# esquematico2.net
KiCad netlist of a schematic drawn in EAGLE
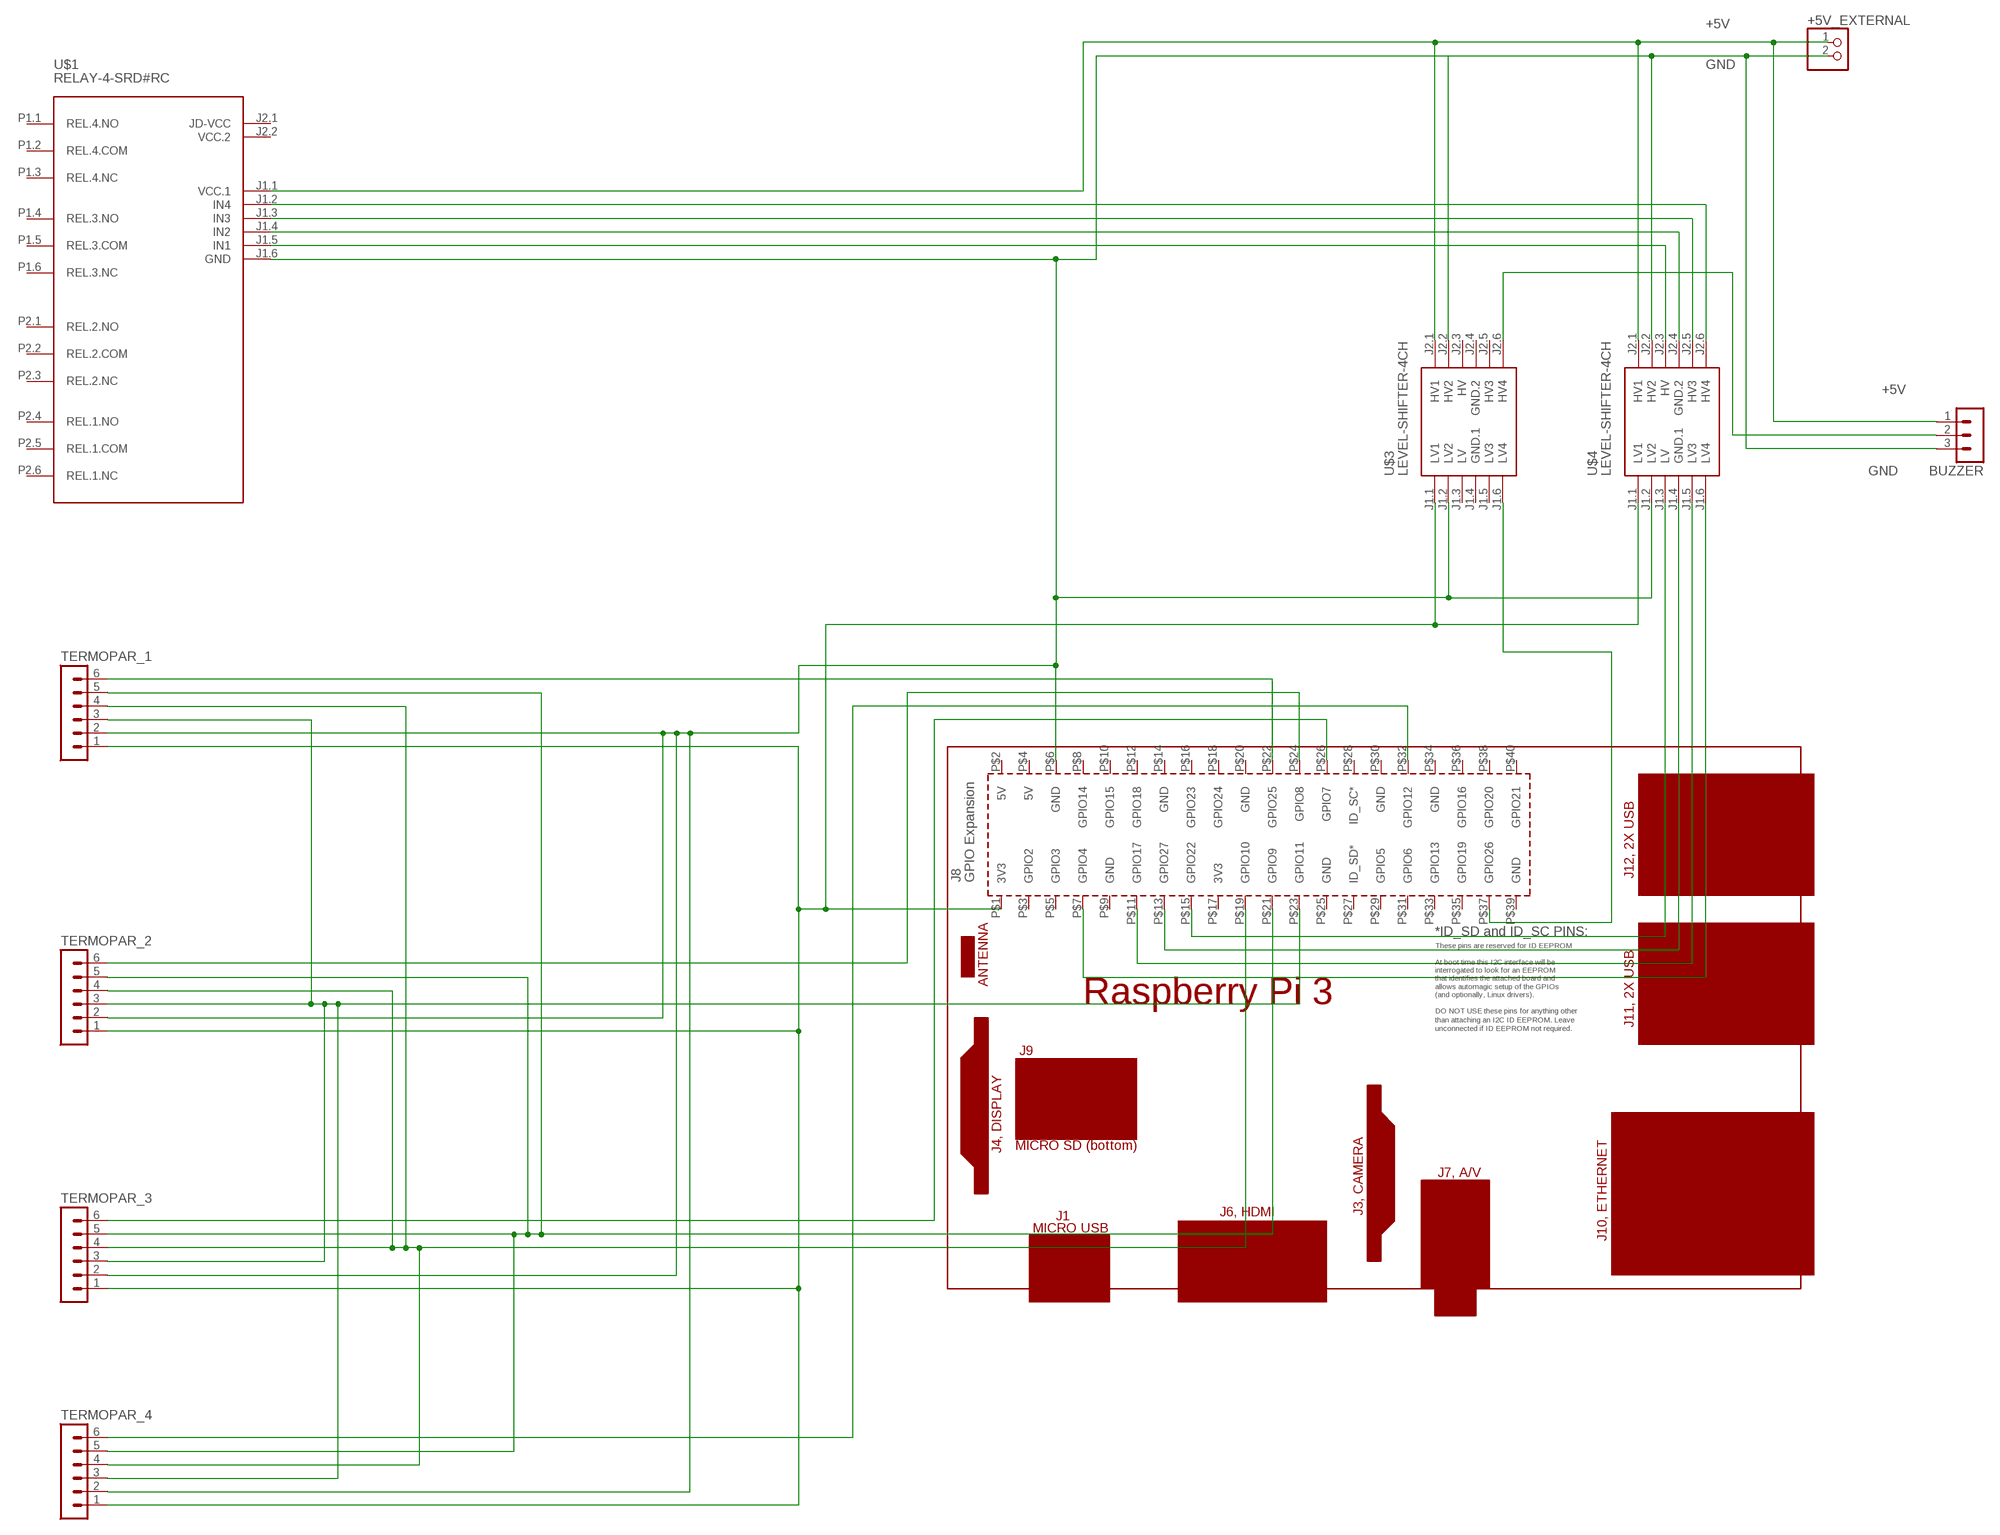
[diagram p0: schematic, sheet 1]

(export (version "E")
  (design (tool "Eeschema 10.0.6"))
  (components
    (comp (ref "+5V_EXTERNAL")
      (value "PINHD-1X2")
      (footprint "eagle-import:1X02")
      (libsource (lib "eagle-import") (part "PINHD-1X2"))
    )
    (comp (ref "BUZZER")
      (value "MA03-1")
      (footprint "eagle-import:MA03-1")
      (libsource (lib "eagle-import") (part "MA03-1"))
    )
    (comp (ref "PCB1")
      (value "RPI3RPI3")
      (footprint "eagle-import:RPI3")
      (libsource (lib "eagle-import") (part "RPI3RPI3"))
    )
    (comp (ref "TERMOPAR_1")
      (value "MA06-1")
      (footprint "eagle-import:MA06-1")
      (libsource (lib "eagle-import") (part "MA06-1"))
    )
    (comp (ref "TERMOPAR_2")
      (value "MA06-1")
      (footprint "eagle-import:MA06-1")
      (libsource (lib "eagle-import") (part "MA06-1"))
    )
    (comp (ref "TERMOPAR_3")
      (value "MA06-1")
      (footprint "eagle-import:MA06-1")
      (libsource (lib "eagle-import") (part "MA06-1"))
    )
    (comp (ref "TERMOPAR_4")
      (value "MA06-1")
      (footprint "eagle-import:MA06-1")
      (libsource (lib "eagle-import") (part "MA06-1"))
    )
    (comp (ref "U$1")
      (value "RELAY-4-SRD#RC")
      (footprint "eagle-import:RELAY-4-SRD#RC")
      (libsource (lib "eagle-import") (part "RELAY-4-SRD#RC"))
    )
    (comp (ref "U$3")
      (value "LEVEL-SHIFTER-4CH")
      (footprint "eagle-import:LEVEL-SHIFTER-4CH")
      (libsource (lib "eagle-import") (part "LEVEL-SHIFTER-4CH"))
    )
    (comp (ref "U$4")
      (value "LEVEL-SHIFTER-4CH")
      (footprint "eagle-import:LEVEL-SHIFTER-4CH")
      (libsource (lib "eagle-import") (part "LEVEL-SHIFTER-4CH"))
    )
  )
  (nets
    (net (code "1") (name "/+5V") (class "Default")
      (node (ref "+5V_EXTERNAL") (pin "1") (pinfunction "1_1") (pintype "passive"))
      (node (ref "BUZZER") (pin "1") (pinfunction "1_1") (pintype "passive"))
      (node (ref "U$1") (pin "J1.1") (pinfunction "VCC.1_J1.1") (pintype "power_in"))
      (node (ref "U$3") (pin "J2.1") (pinfunction "HV1_J2.1") (pintype "bidirectional"))
      (node (ref "U$4") (pin "J2.1") (pinfunction "HV1_J2.1") (pintype "bidirectional"))
    )
    (net (code "2") (name "/GND") (class "Default")
      (node (ref "+5V_EXTERNAL") (pin "2") (pinfunction "2_2") (pintype "passive"))
      (node (ref "BUZZER") (pin "3") (pinfunction "3_3") (pintype "passive"))
      (node (ref "PCB1") (pin "P$6") (pinfunction "GND_P$6") (pintype "bidirectional"))
      (node (ref "TERMOPAR_1") (pin "2") (pinfunction "2_2") (pintype "passive"))
      (node (ref "TERMOPAR_2") (pin "2") (pinfunction "2_2") (pintype "passive"))
      (node (ref "TERMOPAR_3") (pin "2") (pinfunction "2_2") (pintype "passive"))
      (node (ref "TERMOPAR_4") (pin "2") (pinfunction "2_2") (pintype "passive"))
      (node (ref "U$1") (pin "J1.6") (pinfunction "GND_J1.6") (pintype "power_in"))
      (node (ref "U$3") (pin "J1.2") (pinfunction "LV2_J1.2") (pintype "bidirectional"))
      (node (ref "U$3") (pin "J2.2") (pinfunction "HV2_J2.2") (pintype "bidirectional"))
      (node (ref "U$4") (pin "J1.2") (pinfunction "LV2_J1.2") (pintype "bidirectional"))
      (node (ref "U$4") (pin "J2.2") (pinfunction "HV2_J2.2") (pintype "bidirectional"))
    )
    (net (code "3") (name "/GND.1") (class "Default")
      (node (ref "U$3") (pin "J1.4") (pinfunction "GND.1_J1.4") (pintype "power_in"))
    )
    (net (code "4") (name "/GND.2") (class "Default")
      (node (ref "U$3") (pin "J2.4") (pinfunction "GND.2_J2.4") (pintype "power_in"))
    )
    (net (code "5") (name "/HV") (class "Default")
      (node (ref "U$3") (pin "J2.3") (pinfunction "HV_J2.3") (pintype "power_in"))
    )
    (net (code "6") (name "/LV") (class "Default")
      (node (ref "U$3") (pin "J1.3") (pinfunction "LV_J1.3") (pintype "power_in"))
    )
    (net (code "7") (name "/VCC.2") (class "Default")
      (node (ref "U$1") (pin "J2.2") (pinfunction "VCC.2_J2.2") (pintype "power_in"))
    )
    (net (code "8") (name "Net-(PCB1-GPIO4)") (class "Default")
      (node (ref "PCB1") (pin "P$7") (pinfunction "GPIO4_P$7") (pintype "bidirectional"))
      (node (ref "U$4") (pin "J1.6") (pinfunction "LV4_J1.6") (pintype "bidirectional"))
    )
    (net (code "9") (name "Net-(PCB1-GPIO7)") (class "Default")
      (node (ref "PCB1") (pin "P$26") (pinfunction "GPIO7_P$26") (pintype "bidirectional"))
      (node (ref "TERMOPAR_3") (pin "6") (pinfunction "6_6") (pintype "passive"))
    )
    (net (code "10") (name "Net-(PCB1-GPIO8)") (class "Default")
      (node (ref "PCB1") (pin "P$24") (pinfunction "GPIO8_P$24") (pintype "bidirectional"))
      (node (ref "TERMOPAR_2") (pin "6") (pinfunction "6_6") (pintype "passive"))
    )
    (net (code "11") (name "Net-(PCB1-GPIO9)") (class "Default")
      (node (ref "PCB1") (pin "P$21") (pinfunction "GPIO9_P$21") (pintype "bidirectional"))
      (node (ref "TERMOPAR_1") (pin "5") (pinfunction "5_5") (pintype "passive"))
      (node (ref "TERMOPAR_2") (pin "5") (pinfunction "5_5") (pintype "passive"))
      (node (ref "TERMOPAR_3") (pin "5") (pinfunction "5_5") (pintype "passive"))
      (node (ref "TERMOPAR_4") (pin "5") (pinfunction "5_5") (pintype "passive"))
    )
    (net (code "12") (name "Net-(PCB1-GPIO10)") (class "Default")
      (node (ref "PCB1") (pin "P$19") (pinfunction "GPIO10_P$19") (pintype "bidirectional"))
      (node (ref "TERMOPAR_1") (pin "4") (pinfunction "4_4") (pintype "passive"))
      (node (ref "TERMOPAR_2") (pin "4") (pinfunction "4_4") (pintype "passive"))
      (node (ref "TERMOPAR_3") (pin "4") (pinfunction "4_4") (pintype "passive"))
      (node (ref "TERMOPAR_4") (pin "4") (pinfunction "4_4") (pintype "passive"))
    )
    (net (code "13") (name "Net-(PCB1-GPIO11)") (class "Default")
      (node (ref "PCB1") (pin "P$23") (pinfunction "GPIO11_P$23") (pintype "bidirectional"))
      (node (ref "TERMOPAR_1") (pin "3") (pinfunction "3_3") (pintype "passive"))
      (node (ref "TERMOPAR_2") (pin "3") (pinfunction "3_3") (pintype "passive"))
      (node (ref "TERMOPAR_3") (pin "3") (pinfunction "3_3") (pintype "passive"))
      (node (ref "TERMOPAR_4") (pin "3") (pinfunction "3_3") (pintype "passive"))
    )
    (net (code "14") (name "Net-(PCB1-GPIO12)") (class "Default")
      (node (ref "PCB1") (pin "P$32") (pinfunction "GPIO12_P$32") (pintype "bidirectional"))
      (node (ref "TERMOPAR_4") (pin "6") (pinfunction "6_6") (pintype "passive"))
    )
    (net (code "15") (name "Net-(PCB1-GPIO17)") (class "Default")
      (node (ref "PCB1") (pin "P$11") (pinfunction "GPIO17_P$11") (pintype "bidirectional"))
      (node (ref "U$4") (pin "J1.5") (pinfunction "LV3_J1.5") (pintype "bidirectional"))
    )
    (net (code "16") (name "Net-(PCB1-GPIO22)") (class "Default")
      (node (ref "PCB1") (pin "P$15") (pinfunction "GPIO22_P$15") (pintype "bidirectional"))
      (node (ref "U$4") (pin "J1.3") (pinfunction "LV_J1.3") (pintype "power_in"))
    )
    (net (code "17") (name "Net-(PCB1-GPIO25)") (class "Default")
      (node (ref "PCB1") (pin "P$22") (pinfunction "GPIO25_P$22") (pintype "bidirectional"))
      (node (ref "TERMOPAR_1") (pin "6") (pinfunction "6_6") (pintype "passive"))
    )
    (net (code "18") (name "Net-(PCB1-GPIO26)") (class "Default")
      (node (ref "PCB1") (pin "P$37") (pinfunction "GPIO26_P$37") (pintype "bidirectional"))
      (node (ref "U$3") (pin "J1.6") (pinfunction "LV4_J1.6") (pintype "bidirectional"))
    )
    (net (code "19") (name "Net-(PCB1-GPIO27)") (class "Default")
      (node (ref "PCB1") (pin "P$13") (pinfunction "GPIO27_P$13") (pintype "bidirectional"))
      (node (ref "U$4") (pin "J1.4") (pinfunction "GND.1_J1.4") (pintype "power_in"))
    )
    (net (code "20") (name "Net-(U$1-IN1)") (class "Default")
      (node (ref "U$1") (pin "J1.5") (pinfunction "IN1_J1.5") (pintype "bidirectional"))
      (node (ref "U$4") (pin "J2.3") (pinfunction "HV_J2.3") (pintype "power_in"))
    )
    (net (code "21") (name "Net-(U$1-IN2)") (class "Default")
      (node (ref "U$1") (pin "J1.4") (pinfunction "IN2_J1.4") (pintype "bidirectional"))
      (node (ref "U$4") (pin "J2.4") (pinfunction "GND.2_J2.4") (pintype "power_in"))
    )
    (net (code "22") (name "Net-(U$1-IN3)") (class "Default")
      (node (ref "U$1") (pin "J1.3") (pinfunction "IN3_J1.3") (pintype "bidirectional"))
      (node (ref "U$4") (pin "J2.5") (pinfunction "HV3_J2.5") (pintype "bidirectional"))
    )
    (net (code "23") (name "Net-(U$1-IN4)") (class "Default")
      (node (ref "U$1") (pin "J1.2") (pinfunction "IN4_J1.2") (pintype "bidirectional"))
      (node (ref "U$4") (pin "J2.6") (pinfunction "HV4_J2.6") (pintype "bidirectional"))
    )
    (net (code "24") (name "Net-(U$3-HV4)") (class "Default")
      (node (ref "BUZZER") (pin "2") (pinfunction "2_2") (pintype "passive"))
      (node (ref "U$3") (pin "J2.6") (pinfunction "HV4_J2.6") (pintype "bidirectional"))
    )
    (net (code "25") (name "Net-(U$3-LV1)") (class "Default")
      (node (ref "PCB1") (pin "P$1") (pinfunction "3V3_P$1") (pintype "bidirectional"))
      (node (ref "TERMOPAR_1") (pin "1") (pinfunction "1_1") (pintype "passive"))
      (node (ref "TERMOPAR_2") (pin "1") (pinfunction "1_1") (pintype "passive"))
      (node (ref "TERMOPAR_3") (pin "1") (pinfunction "1_1") (pintype "passive"))
      (node (ref "TERMOPAR_4") (pin "1") (pinfunction "1_1") (pintype "passive"))
      (node (ref "U$3") (pin "J1.1") (pinfunction "LV1_J1.1") (pintype "bidirectional"))
      (node (ref "U$4") (pin "J1.1") (pinfunction "LV1_J1.1") (pintype "bidirectional"))
    )
    (net (code "26") (name "unconnected-(PCB1-3V3-PadP$17)") (class "Default")
      (node (ref "PCB1") (pin "P$17") (pinfunction "3V3_P$17") (pintype "bidirectional"))
    )
    (net (code "27") (name "unconnected-(PCB1-5V-PadP$2)") (class "Default")
      (node (ref "PCB1") (pin "P$2") (pinfunction "5V_P$2") (pintype "bidirectional"))
    )
    (net (code "28") (name "unconnected-(PCB1-5V-PadP$4)") (class "Default")
      (node (ref "PCB1") (pin "P$4") (pinfunction "5V_P$4") (pintype "bidirectional"))
    )
    (net (code "29") (name "unconnected-(PCB1-GND-PadP$9)") (class "Default")
      (node (ref "PCB1") (pin "P$9") (pinfunction "GND_P$9") (pintype "bidirectional"))
    )
    (net (code "30") (name "unconnected-(PCB1-GND-PadP$14)") (class "Default")
      (node (ref "PCB1") (pin "P$14") (pinfunction "GND_P$14") (pintype "bidirectional"))
    )
    (net (code "31") (name "unconnected-(PCB1-GND-PadP$20)") (class "Default")
      (node (ref "PCB1") (pin "P$20") (pinfunction "GND_P$20") (pintype "bidirectional"))
    )
    (net (code "32") (name "unconnected-(PCB1-GND-PadP$25)") (class "Default")
      (node (ref "PCB1") (pin "P$25") (pinfunction "GND_P$25") (pintype "bidirectional"))
    )
    (net (code "33") (name "unconnected-(PCB1-GND-PadP$30)") (class "Default")
      (node (ref "PCB1") (pin "P$30") (pinfunction "GND_P$30") (pintype "bidirectional"))
    )
    (net (code "34") (name "unconnected-(PCB1-GND-PadP$34)") (class "Default")
      (node (ref "PCB1") (pin "P$34") (pinfunction "GND_P$34") (pintype "bidirectional"))
    )
    (net (code "35") (name "unconnected-(PCB1-GND-PadP$39)") (class "Default")
      (node (ref "PCB1") (pin "P$39") (pinfunction "GND_P$39") (pintype "bidirectional"))
    )
    (net (code "36") (name "unconnected-(PCB1-GPIO2-PadP$3)") (class "Default")
      (node (ref "PCB1") (pin "P$3") (pinfunction "GPIO2_P$3") (pintype "bidirectional"))
    )
    (net (code "37") (name "unconnected-(PCB1-GPIO3-PadP$5)") (class "Default")
      (node (ref "PCB1") (pin "P$5") (pinfunction "GPIO3_P$5") (pintype "bidirectional"))
    )
    (net (code "38") (name "unconnected-(PCB1-GPIO5-PadP$29)") (class "Default")
      (node (ref "PCB1") (pin "P$29") (pinfunction "GPIO5_P$29") (pintype "bidirectional"))
    )
    (net (code "39") (name "unconnected-(PCB1-GPIO6-PadP$31)") (class "Default")
      (node (ref "PCB1") (pin "P$31") (pinfunction "GPIO6_P$31") (pintype "bidirectional"))
    )
    (net (code "40") (name "unconnected-(PCB1-GPIO13-PadP$33)") (class "Default")
      (node (ref "PCB1") (pin "P$33") (pinfunction "GPIO13_P$33") (pintype "bidirectional"))
    )
    (net (code "41") (name "unconnected-(PCB1-GPIO14-PadP$8)") (class "Default")
      (node (ref "PCB1") (pin "P$8") (pinfunction "GPIO14_P$8") (pintype "bidirectional"))
    )
    (net (code "42") (name "unconnected-(PCB1-GPIO15-PadP$10)") (class "Default")
      (node (ref "PCB1") (pin "P$10") (pinfunction "GPIO15_P$10") (pintype "bidirectional"))
    )
    (net (code "43") (name "unconnected-(PCB1-GPIO16-PadP$36)") (class "Default")
      (node (ref "PCB1") (pin "P$36") (pinfunction "GPIO16_P$36") (pintype "bidirectional"))
    )
    (net (code "44") (name "unconnected-(PCB1-GPIO18-PadP$12)") (class "Default")
      (node (ref "PCB1") (pin "P$12") (pinfunction "GPIO18_P$12") (pintype "bidirectional"))
    )
    (net (code "45") (name "unconnected-(PCB1-GPIO19-PadP$35)") (class "Default")
      (node (ref "PCB1") (pin "P$35") (pinfunction "GPIO19_P$35") (pintype "bidirectional"))
    )
    (net (code "46") (name "unconnected-(PCB1-GPIO20-PadP$38)") (class "Default")
      (node (ref "PCB1") (pin "P$38") (pinfunction "GPIO20_P$38") (pintype "bidirectional"))
    )
    (net (code "47") (name "unconnected-(PCB1-GPIO21-PadP$40)") (class "Default")
      (node (ref "PCB1") (pin "P$40") (pinfunction "GPIO21_P$40") (pintype "bidirectional"))
    )
    (net (code "48") (name "unconnected-(PCB1-GPIO23-PadP$16)") (class "Default")
      (node (ref "PCB1") (pin "P$16") (pinfunction "GPIO23_P$16") (pintype "bidirectional"))
    )
    (net (code "49") (name "unconnected-(PCB1-GPIO24-PadP$18)") (class "Default")
      (node (ref "PCB1") (pin "P$18") (pinfunction "GPIO24_P$18") (pintype "bidirectional"))
    )
    (net (code "50") (name "unconnected-(PCB1-ID_SC*-PadP$28)") (class "Default")
      (node (ref "PCB1") (pin "P$28") (pinfunction "ID_SC*_P$28") (pintype "bidirectional"))
    )
    (net (code "51") (name "unconnected-(PCB1-ID_SD*-PadP$27)") (class "Default")
      (node (ref "PCB1") (pin "P$27") (pinfunction "ID_SD*_P$27") (pintype "bidirectional"))
    )
    (net (code "52") (name "unconnected-(U$1-JD-VCC-PadJ2.1)") (class "Default")
      (node (ref "U$1") (pin "J2.1") (pinfunction "JD-VCC_J2.1") (pintype "bidirectional"))
    )
    (net (code "53") (name "unconnected-(U$1-REL.1.COM-PadP2.5)") (class "Default")
      (node (ref "U$1") (pin "P2.5") (pinfunction "REL.1.COM_P2.5") (pintype "bidirectional"))
    )
    (net (code "54") (name "unconnected-(U$1-REL.1.NC-PadP2.6)") (class "Default")
      (node (ref "U$1") (pin "P2.6") (pinfunction "REL.1.NC_P2.6") (pintype "bidirectional"))
    )
    (net (code "55") (name "unconnected-(U$1-REL.1.NO-PadP2.4)") (class "Default")
      (node (ref "U$1") (pin "P2.4") (pinfunction "REL.1.NO_P2.4") (pintype "bidirectional"))
    )
    (net (code "56") (name "unconnected-(U$1-REL.2.COM-PadP2.2)") (class "Default")
      (node (ref "U$1") (pin "P2.2") (pinfunction "REL.2.COM_P2.2") (pintype "bidirectional"))
    )
    (net (code "57") (name "unconnected-(U$1-REL.2.NC-PadP2.3)") (class "Default")
      (node (ref "U$1") (pin "P2.3") (pinfunction "REL.2.NC_P2.3") (pintype "bidirectional"))
    )
    (net (code "58") (name "unconnected-(U$1-REL.2.NO-PadP2.1)") (class "Default")
      (node (ref "U$1") (pin "P2.1") (pinfunction "REL.2.NO_P2.1") (pintype "bidirectional"))
    )
    (net (code "59") (name "unconnected-(U$1-REL.3.COM-PadP1.5)") (class "Default")
      (node (ref "U$1") (pin "P1.5") (pinfunction "REL.3.COM_P1.5") (pintype "bidirectional"))
    )
    (net (code "60") (name "unconnected-(U$1-REL.3.NC-PadP1.6)") (class "Default")
      (node (ref "U$1") (pin "P1.6") (pinfunction "REL.3.NC_P1.6") (pintype "bidirectional"))
    )
    (net (code "61") (name "unconnected-(U$1-REL.3.NO-PadP1.4)") (class "Default")
      (node (ref "U$1") (pin "P1.4") (pinfunction "REL.3.NO_P1.4") (pintype "bidirectional"))
    )
    (net (code "62") (name "unconnected-(U$1-REL.4.COM-PadP1.2)") (class "Default")
      (node (ref "U$1") (pin "P1.2") (pinfunction "REL.4.COM_P1.2") (pintype "bidirectional"))
    )
    (net (code "63") (name "unconnected-(U$1-REL.4.NC-PadP1.3)") (class "Default")
      (node (ref "U$1") (pin "P1.3") (pinfunction "REL.4.NC_P1.3") (pintype "bidirectional"))
    )
    (net (code "64") (name "unconnected-(U$1-REL.4.NO-PadP1.1)") (class "Default")
      (node (ref "U$1") (pin "P1.1") (pinfunction "REL.4.NO_P1.1") (pintype "bidirectional"))
    )
    (net (code "65") (name "unconnected-(U$3-HV3-PadJ2.5)") (class "Default")
      (node (ref "U$3") (pin "J2.5") (pinfunction "HV3_J2.5") (pintype "bidirectional"))
    )
    (net (code "66") (name "unconnected-(U$3-LV3-PadJ1.5)") (class "Default")
      (node (ref "U$3") (pin "J1.5") (pinfunction "LV3_J1.5") (pintype "bidirectional"))
    )
  )
)
